# LedStrip_Adapter.net
KiCad netlist of a schematic drawn in EAGLE
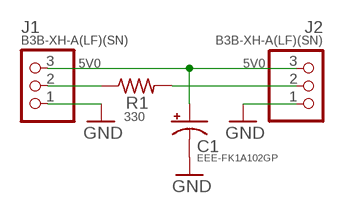
[diagram p0: schematic, sheet 1]

(export (version "E")
  (design (tool "Eeschema 10.0.6"))
  (components
    (comp (ref "C1")
      (value "EEE-FK1A102GP")
      (footprint "eagle-import:PANASONIC_CAP_G")
      (libsource (lib "eagle-import") (part "EEE-FC1H470P"))
    )
    (comp (ref "J1")
      (value "B3B-XH-A(LF)(SN)")
      (footprint "eagle-import:B3B-XH-A(LF)(SN)")
      (libsource (lib "eagle-import") (part "B3B-XH-A(LF)(SN)"))
    )
    (comp (ref "J2")
      (value "B3B-XH-A(LF)(SN)")
      (footprint "eagle-import:B3B-XH-A(LF)(SN)")
      (libsource (lib "eagle-import") (part "B3B-XH-A(LF)(SN)"))
    )
    (comp (ref "R1")
      (value "330")
      (footprint "eagle-import:0603")
      (libsource (lib "eagle-import") (part "R0603"))
    )
  )
  (nets
    (net (code "1") (name "/5V0") (class "Default")
      (node (ref "C1") (pin "POS") (pinfunction "+_POS") (pintype "passive"))
      (node (ref "J1") (pin "3") (pinfunction "3_3") (pintype "passive"))
      (node (ref "J2") (pin "3") (pinfunction "3_3") (pintype "passive"))
    )
    (net (code "2") (name "GND") (class "Default")
      (node (ref "C1") (pin "NEG") (pinfunction "-_NEG") (pintype "passive"))
      (node (ref "J1") (pin "1") (pinfunction "1_1") (pintype "passive"))
      (node (ref "J2") (pin "1") (pinfunction "1_1") (pintype "passive"))
    )
    (net (code "3") (name "Net-(J1-Pad2)") (class "Default")
      (node (ref "J1") (pin "2") (pinfunction "2_2") (pintype "passive"))
      (node (ref "R1") (pin "1") (pinfunction "1_1") (pintype "passive"))
    )
    (net (code "4") (name "Net-(J2-Pad2)") (class "Default")
      (node (ref "J2") (pin "2") (pinfunction "2_2") (pintype "passive"))
      (node (ref "R1") (pin "2") (pinfunction "2_2") (pintype "passive"))
    )
  )
)
